# Sheet2.net
KiCad netlist of a schematic drawn in Altium Designer
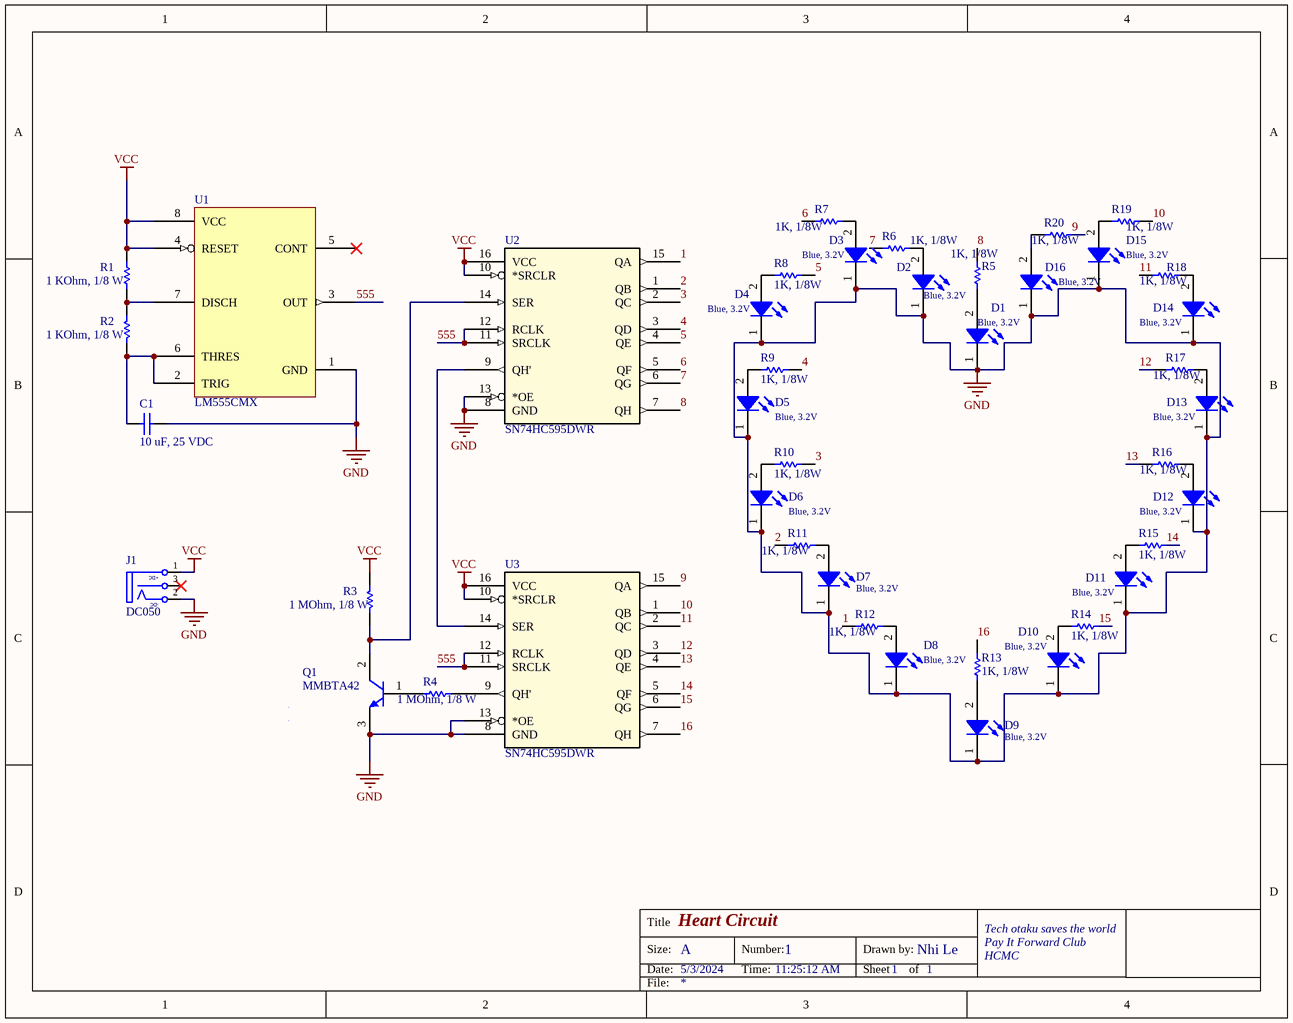
[diagram p0: Sheet2.SchDoc]

(export (version "E")
  (design (tool "Eeschema 10.0.6"))
  (components
    (comp (ref "C1")
      (value "10 uF, 25 VDC")
      (footprint "CAP_0805")
      (description "CAP, size 0805, 10 uF, 25 VDC")
      (fields (field (name "TOLERANCE") "+/-10%"))
      (libsource (lib "Altium_Ceramic_Cap") (part "0108051061025"))
    )
    (comp (ref "D1")
      (value "Blue, 3.2V")
      (footprint "WL-SMCW_0805")
      (description "WL-SMCW SMT Mono-color Chip LED Waterclear, size 0805, Blue, 3.2V, 140deg")
      (libsource (lib "Altium_LED") (part "160805BlueClear"))
    )
    (comp (ref "D2")
      (value "Blue, 3.2V")
      (footprint "WL-SMCW_0805")
      (description "WL-SMCW SMT Mono-color Chip LED Waterclear, size 0805, Blue, 3.2V, 140deg")
      (libsource (lib "Altium_LED") (part "160805BlueClear"))
    )
    (comp (ref "D3")
      (value "Blue, 3.2V")
      (footprint "WL-SMCW_0805")
      (description "WL-SMCW SMT Mono-color Chip LED Waterclear, size 0805, Blue, 3.2V, 140deg")
      (libsource (lib "Altium_LED") (part "160805BlueClear"))
    )
    (comp (ref "D4")
      (value "Blue, 3.2V")
      (footprint "WL-SMCW_0805")
      (description "WL-SMCW SMT Mono-color Chip LED Waterclear, size 0805, Blue, 3.2V, 140deg")
      (libsource (lib "Altium_LED") (part "160805BlueClear"))
    )
    (comp (ref "D5")
      (value "Blue, 3.2V")
      (footprint "WL-SMCW_0805")
      (description "WL-SMCW SMT Mono-color Chip LED Waterclear, size 0805, Blue, 3.2V, 140deg")
      (libsource (lib "Altium_LED") (part "160805BlueClear"))
    )
    (comp (ref "D6")
      (value "Blue, 3.2V")
      (footprint "WL-SMCW_0805")
      (description "WL-SMCW SMT Mono-color Chip LED Waterclear, size 0805, Blue, 3.2V, 140deg")
      (libsource (lib "Altium_LED") (part "160805BlueClear"))
    )
    (comp (ref "D7")
      (value "Blue, 3.2V")
      (footprint "WL-SMCW_0805")
      (description "WL-SMCW SMT Mono-color Chip LED Waterclear, size 0805, Blue, 3.2V, 140deg")
      (libsource (lib "Altium_LED") (part "160805BlueClear"))
    )
    (comp (ref "D8")
      (value "Blue, 3.2V")
      (footprint "WL-SMCW_0805")
      (description "WL-SMCW SMT Mono-color Chip LED Waterclear, size 0805, Blue, 3.2V, 140deg")
      (libsource (lib "Altium_LED") (part "160805BlueClear"))
    )
    (comp (ref "D9")
      (value "Blue, 3.2V")
      (footprint "WL-SMCW_0805")
      (description "WL-SMCW SMT Mono-color Chip LED Waterclear, size 0805, Blue, 3.2V, 140deg")
      (libsource (lib "Altium_LED") (part "160805BlueClear"))
    )
    (comp (ref "D10")
      (value "Blue, 3.2V")
      (footprint "WL-SMCW_0805")
      (description "WL-SMCW SMT Mono-color Chip LED Waterclear, size 0805, Blue, 3.2V, 140deg")
      (libsource (lib "Altium_LED") (part "160805BlueClear"))
    )
    (comp (ref "D11")
      (value "Blue, 3.2V")
      (footprint "WL-SMCW_0805")
      (description "WL-SMCW SMT Mono-color Chip LED Waterclear, size 0805, Blue, 3.2V, 140deg")
      (libsource (lib "Altium_LED") (part "160805BlueClear"))
    )
    (comp (ref "D12")
      (value "Blue, 3.2V")
      (footprint "WL-SMCW_0805")
      (description "WL-SMCW SMT Mono-color Chip LED Waterclear, size 0805, Blue, 3.2V, 140deg")
      (libsource (lib "Altium_LED") (part "160805BlueClear"))
    )
    (comp (ref "D13")
      (value "Blue, 3.2V")
      (footprint "WL-SMCW_0805")
      (description "WL-SMCW SMT Mono-color Chip LED Waterclear, size 0805, Blue, 3.2V, 140deg")
      (libsource (lib "Altium_LED") (part "160805BlueClear"))
    )
    (comp (ref "D14")
      (value "Blue, 3.2V")
      (footprint "WL-SMCW_0805")
      (description "WL-SMCW SMT Mono-color Chip LED Waterclear, size 0805, Blue, 3.2V, 140deg")
      (libsource (lib "Altium_LED") (part "160805BlueClear"))
    )
    (comp (ref "D15")
      (value "Blue, 3.2V")
      (footprint "WL-SMCW_0805")
      (description "WL-SMCW SMT Mono-color Chip LED Waterclear, size 0805, Blue, 3.2V, 140deg")
      (libsource (lib "Altium_LED") (part "160805BlueClear"))
    )
    (comp (ref "D16")
      (value "Blue, 3.2V")
      (footprint "WL-SMCW_0805")
      (description "WL-SMCW SMT Mono-color Chip LED Waterclear, size 0805, Blue, 3.2V, 140deg")
      (libsource (lib "Altium_LED") (part "160805BlueClear"))
    )
    (comp (ref "J1")
      (value "DC050")
      (footprint "DC050")
      (fields (field (name "MANUFACTURER") "OEM"))
      (libsource (lib "Altium_AC_DC_Jack") (part "DC050"))
    )
    (comp (ref "Q1")
      (value "MMBTA42")
      (footprint "MMBT-SOT23")
      (description "TRANS NPN, 300V, 0.5A, SOT23-3")
      (libsource (lib "Altium_BJT") (part "MMBTA42"))
    )
    (comp (ref "R1")
      (value "1 KOhm, 1/8 W")
      (footprint "RESISTOR_0805")
      (description "RES, size 0805, 1 KOhm, 1/8 W")
      (libsource (lib "Altium_Resistor") (part "0008051021"))
    )
    (comp (ref "R2")
      (value "1 KOhm, 1/8 W")
      (footprint "RESISTOR_0805")
      (description "RES, size 0805, 1 KOhm, 1/8 W")
      (libsource (lib "Altium_Resistor") (part "0008051021"))
    )
    (comp (ref "R3")
      (value "1 MOhm, 1/8 W")
      (footprint "RESISTOR_0805")
      (description "RES, size 0805, 1 MOhm, 1/8 W")
      (libsource (lib "Altium_Resistor") (part "0008051051"))
    )
    (comp (ref "R4")
      (value "1 MOhm, 1/8 W")
      (footprint "RESISTOR_0805")
      (description "RES, size 0805, 1 MOhm, 1/8 W")
      (libsource (lib "Altium_Resistor") (part "0008051051"))
    )
    (comp (ref "R5")
      (value "1K, 1/8W")
      (footprint "RESISTOR_0805")
      (description "RES, size 0805, 1 KOhm, 1/8 W")
      (libsource (lib "Altium_Resistor") (part "0008051021"))
    )
    (comp (ref "R6")
      (value "1K, 1/8W")
      (footprint "RESISTOR_0805")
      (description "RES, size 0805, 1 KOhm, 1/8 W")
      (libsource (lib "Altium_Resistor") (part "0008051021"))
    )
    (comp (ref "R7")
      (value "1K, 1/8W")
      (footprint "RESISTOR_0805")
      (description "RES, size 0805, 1 KOhm, 1/8 W")
      (libsource (lib "Altium_Resistor") (part "0008051021"))
    )
    (comp (ref "R8")
      (value "1K, 1/8W")
      (footprint "RESISTOR_0805")
      (description "RES, size 0805, 1 KOhm, 1/8 W")
      (libsource (lib "Altium_Resistor") (part "0008051021"))
    )
    (comp (ref "R9")
      (value "1K, 1/8W")
      (footprint "RESISTOR_0805")
      (description "RES, size 0805, 1 KOhm, 1/8 W")
      (libsource (lib "Altium_Resistor") (part "0008051021"))
    )
    (comp (ref "R10")
      (value "1K, 1/8W")
      (footprint "RESISTOR_0805")
      (description "RES, size 0805, 1 KOhm, 1/8 W")
      (libsource (lib "Altium_Resistor") (part "0008051021"))
    )
    (comp (ref "R11")
      (value "1K, 1/8W")
      (footprint "RESISTOR_0805")
      (description "RES, size 0805, 1 KOhm, 1/8 W")
      (libsource (lib "Altium_Resistor") (part "0008051021"))
    )
    (comp (ref "R12")
      (value "1K, 1/8W")
      (footprint "RESISTOR_0805")
      (description "RES, size 0805, 1 KOhm, 1/8 W")
      (libsource (lib "Altium_Resistor") (part "0008051021"))
    )
    (comp (ref "R13")
      (value "1K, 1/8W")
      (footprint "RESISTOR_0805")
      (description "RES, size 0805, 1 KOhm, 1/8 W")
      (libsource (lib "Altium_Resistor") (part "0008051021"))
    )
    (comp (ref "R14")
      (value "1K, 1/8W")
      (footprint "RESISTOR_0805")
      (description "RES, size 0805, 1 KOhm, 1/8 W")
      (libsource (lib "Altium_Resistor") (part "0008051021"))
    )
    (comp (ref "R15")
      (value "1K, 1/8W")
      (footprint "RESISTOR_0805")
      (description "RES, size 0805, 1 KOhm, 1/8 W")
      (libsource (lib "Altium_Resistor") (part "0008051021"))
    )
    (comp (ref "R16")
      (value "1K, 1/8W")
      (footprint "RESISTOR_0805")
      (description "RES, size 0805, 1 KOhm, 1/8 W")
      (libsource (lib "Altium_Resistor") (part "0008051021"))
    )
    (comp (ref "R17")
      (value "1K, 1/8W")
      (footprint "RESISTOR_0805")
      (description "RES, size 0805, 1 KOhm, 1/8 W")
      (libsource (lib "Altium_Resistor") (part "0008051021"))
    )
    (comp (ref "R18")
      (value "1K, 1/8W")
      (footprint "RESISTOR_0805")
      (description "RES, size 0805, 1 KOhm, 1/8 W")
      (libsource (lib "Altium_Resistor") (part "0008051021"))
    )
    (comp (ref "R19")
      (value "1K, 1/8W")
      (footprint "RESISTOR_0805")
      (description "RES, size 0805, 1 KOhm, 1/8 W")
      (libsource (lib "Altium_Resistor") (part "0008051021"))
    )
    (comp (ref "R20")
      (value "1K, 1/8W")
      (footprint "RESISTOR_0805")
      (description "RES, size 0805, 1 KOhm, 1/8 W")
      (libsource (lib "Altium_Resistor") (part "0008051021"))
    )
    (comp (ref "U1")
      (value "LM555CMX")
      (footprint "LM555CMX")
      (description "Timers & Support Products TIMER")
      (fields
        (field (name "MANUFACTURER") "Texas Instruments")
        (field (name "MANUFACTURER PART NUMBER") "LM555CMX/NOPB")
      )
      (libsource (lib "Other") (part "LM555CMX"))
    )
    (comp (ref "U2")
      (value "SN74HC595DWR")
      (footprint "DW16")
      (description "No Description Available")
      (libsource (lib "SN74HC595DWR") (part "SN74HC595DWR"))
    )
    (comp (ref "U3")
      (value "SN74HC595DWR")
      (footprint "DW16")
      (description "No Description Available")
      (libsource (lib "SN74HC595DWR") (part "SN74HC595DWR"))
    )
  )
  (nets
    (net (code "1") (name "/1") (class "Default")
      (node (ref "R12") (pin "2") (pinfunction "2_2") (pintype "passive"))
      (node (ref "U2") (pin "15") (pinfunction "QA_15") (pintype "output"))
    )
    (net (code "2") (name "/2") (class "Default")
      (node (ref "R11") (pin "2") (pinfunction "2_2") (pintype "passive"))
      (node (ref "U2") (pin "1") (pinfunction "QB_1") (pintype "output"))
    )
    (net (code "3") (name "/3") (class "Default")
      (node (ref "R10") (pin "2") (pinfunction "2_2") (pintype "passive"))
      (node (ref "U2") (pin "2") (pinfunction "QC_2") (pintype "output"))
    )
    (net (code "4") (name "/4") (class "Default")
      (node (ref "R9") (pin "2") (pinfunction "2_2") (pintype "passive"))
      (node (ref "U2") (pin "3") (pinfunction "QD_3") (pintype "output"))
    )
    (net (code "5") (name "/5") (class "Default")
      (node (ref "R8") (pin "2") (pinfunction "2_2") (pintype "passive"))
      (node (ref "U2") (pin "4") (pinfunction "QE_4") (pintype "output"))
    )
    (net (code "6") (name "/6") (class "Default")
      (node (ref "R7") (pin "2") (pinfunction "2_2") (pintype "passive"))
      (node (ref "U2") (pin "5") (pinfunction "QF_5") (pintype "output"))
    )
    (net (code "7") (name "/7") (class "Default")
      (node (ref "R6") (pin "2") (pinfunction "2_2") (pintype "passive"))
      (node (ref "U2") (pin "6") (pinfunction "QG_6") (pintype "output"))
    )
    (net (code "8") (name "/8") (class "Default")
      (node (ref "R5") (pin "1") (pinfunction "1_1") (pintype "passive"))
      (node (ref "U2") (pin "7") (pinfunction "QH_7") (pintype "output"))
    )
    (net (code "9") (name "/9") (class "Default")
      (node (ref "R20") (pin "2") (pinfunction "2_2") (pintype "passive"))
      (node (ref "U3") (pin "15") (pinfunction "QA_15") (pintype "output"))
    )
    (net (code "10") (name "/10") (class "Default")
      (node (ref "R19") (pin "2") (pinfunction "2_2") (pintype "passive"))
      (node (ref "U3") (pin "1") (pinfunction "QB_1") (pintype "output"))
    )
    (net (code "11") (name "/11") (class "Default")
      (node (ref "R18") (pin "2") (pinfunction "2_2") (pintype "passive"))
      (node (ref "U3") (pin "2") (pinfunction "QC_2") (pintype "output"))
    )
    (net (code "12") (name "/12") (class "Default")
      (node (ref "R17") (pin "2") (pinfunction "2_2") (pintype "passive"))
      (node (ref "U3") (pin "3") (pinfunction "QD_3") (pintype "output"))
    )
    (net (code "13") (name "/13") (class "Default")
      (node (ref "R16") (pin "2") (pinfunction "2_2") (pintype "passive"))
      (node (ref "U3") (pin "4") (pinfunction "QE_4") (pintype "output"))
    )
    (net (code "14") (name "/14") (class "Default")
      (node (ref "R15") (pin "2") (pinfunction "2_2") (pintype "passive"))
      (node (ref "U3") (pin "5") (pinfunction "QF_5") (pintype "output"))
    )
    (net (code "15") (name "/15") (class "Default")
      (node (ref "R14") (pin "2") (pinfunction "2_2") (pintype "passive"))
      (node (ref "U3") (pin "6") (pinfunction "QG_6") (pintype "output"))
    )
    (net (code "16") (name "/16") (class "Default")
      (node (ref "R13") (pin "2") (pinfunction "2_2") (pintype "passive"))
      (node (ref "U3") (pin "7") (pinfunction "QH_7") (pintype "output"))
    )
    (net (code "17") (name "/555") (class "Default")
      (node (ref "U1") (pin "3") (pinfunction "OUT_3") (pintype "output"))
      (node (ref "U2") (pin "11") (pinfunction "SRCLK_11") (pintype "input"))
      (node (ref "U2") (pin "12") (pinfunction "RCLK_12") (pintype "input"))
      (node (ref "U3") (pin "11") (pinfunction "SRCLK_11") (pintype "input"))
      (node (ref "U3") (pin "12") (pinfunction "RCLK_12") (pintype "input"))
    )
    (net (code "18") (name "GND") (class "Default")
      (node (ref "C1") (pin "2") (pinfunction "2_2") (pintype "passive"))
      (node (ref "D1") (pin "1") (pinfunction "K_1") (pintype "passive"))
      (node (ref "D10") (pin "1") (pinfunction "K_1") (pintype "passive"))
      (node (ref "D11") (pin "1") (pinfunction "K_1") (pintype "passive"))
      (node (ref "D12") (pin "1") (pinfunction "K_1") (pintype "passive"))
      (node (ref "D13") (pin "1") (pinfunction "K_1") (pintype "passive"))
      (node (ref "D14") (pin "1") (pinfunction "K_1") (pintype "passive"))
      (node (ref "D15") (pin "1") (pinfunction "K_1") (pintype "passive"))
      (node (ref "D16") (pin "1") (pinfunction "K_1") (pintype "passive"))
      (node (ref "D2") (pin "1") (pinfunction "K_1") (pintype "passive"))
      (node (ref "D3") (pin "1") (pinfunction "K_1") (pintype "passive"))
      (node (ref "D4") (pin "1") (pinfunction "K_1") (pintype "passive"))
      (node (ref "D5") (pin "1") (pinfunction "K_1") (pintype "passive"))
      (node (ref "D6") (pin "1") (pinfunction "K_1") (pintype "passive"))
      (node (ref "D7") (pin "1") (pinfunction "K_1") (pintype "passive"))
      (node (ref "D8") (pin "1") (pinfunction "K_1") (pintype "passive"))
      (node (ref "D9") (pin "1") (pinfunction "K_1") (pintype "passive"))
      (node (ref "J1") (pin "2") (pinfunction "TN_2") (pintype "passive"))
      (node (ref "Q1") (pin "3") (pinfunction "E_3") (pintype "passive"))
      (node (ref "U1") (pin "1") (pinfunction "GND_1") (pintype "power_in"))
      (node (ref "U2") (pin "13") (pinfunction "*OE_13") (pintype "input"))
      (node (ref "U2") (pin "8") (pinfunction "GND_8") (pintype "power_in"))
      (node (ref "U3") (pin "13") (pinfunction "*OE_13") (pintype "input"))
      (node (ref "U3") (pin "8") (pinfunction "GND_8") (pintype "power_in"))
    )
    (net (code "19") (name "Net-(D1-A)") (class "Default")
      (node (ref "D1") (pin "2") (pinfunction "A_2") (pintype "passive"))
      (node (ref "R5") (pin "2") (pinfunction "2_2") (pintype "passive"))
    )
    (net (code "20") (name "Net-(D2-A)") (class "Default")
      (node (ref "D2") (pin "2") (pinfunction "A_2") (pintype "passive"))
      (node (ref "R6") (pin "1") (pinfunction "1_1") (pintype "passive"))
    )
    (net (code "21") (name "Net-(D3-A)") (class "Default")
      (node (ref "D3") (pin "2") (pinfunction "A_2") (pintype "passive"))
      (node (ref "R7") (pin "1") (pinfunction "1_1") (pintype "passive"))
    )
    (net (code "22") (name "Net-(D4-A)") (class "Default")
      (node (ref "D4") (pin "2") (pinfunction "A_2") (pintype "passive"))
      (node (ref "R8") (pin "1") (pinfunction "1_1") (pintype "passive"))
    )
    (net (code "23") (name "Net-(D5-A)") (class "Default")
      (node (ref "D5") (pin "2") (pinfunction "A_2") (pintype "passive"))
      (node (ref "R9") (pin "1") (pinfunction "1_1") (pintype "passive"))
    )
    (net (code "24") (name "Net-(D6-A)") (class "Default")
      (node (ref "D6") (pin "2") (pinfunction "A_2") (pintype "passive"))
      (node (ref "R10") (pin "1") (pinfunction "1_1") (pintype "passive"))
    )
    (net (code "25") (name "Net-(D7-A)") (class "Default")
      (node (ref "D7") (pin "2") (pinfunction "A_2") (pintype "passive"))
      (node (ref "R11") (pin "1") (pinfunction "1_1") (pintype "passive"))
    )
    (net (code "26") (name "Net-(D8-A)") (class "Default")
      (node (ref "D8") (pin "2") (pinfunction "A_2") (pintype "passive"))
      (node (ref "R12") (pin "1") (pinfunction "1_1") (pintype "passive"))
    )
    (net (code "27") (name "Net-(D9-A)") (class "Default")
      (node (ref "D9") (pin "2") (pinfunction "A_2") (pintype "passive"))
      (node (ref "R13") (pin "1") (pinfunction "1_1") (pintype "passive"))
    )
    (net (code "28") (name "Net-(D10-A)") (class "Default")
      (node (ref "D10") (pin "2") (pinfunction "A_2") (pintype "passive"))
      (node (ref "R14") (pin "1") (pinfunction "1_1") (pintype "passive"))
    )
    (net (code "29") (name "Net-(D11-A)") (class "Default")
      (node (ref "D11") (pin "2") (pinfunction "A_2") (pintype "passive"))
      (node (ref "R15") (pin "1") (pinfunction "1_1") (pintype "passive"))
    )
    (net (code "30") (name "Net-(D12-A)") (class "Default")
      (node (ref "D12") (pin "2") (pinfunction "A_2") (pintype "passive"))
      (node (ref "R16") (pin "1") (pinfunction "1_1") (pintype "passive"))
    )
    (net (code "31") (name "Net-(D13-A)") (class "Default")
      (node (ref "D13") (pin "2") (pinfunction "A_2") (pintype "passive"))
      (node (ref "R17") (pin "1") (pinfunction "1_1") (pintype "passive"))
    )
    (net (code "32") (name "Net-(D14-A)") (class "Default")
      (node (ref "D14") (pin "2") (pinfunction "A_2") (pintype "passive"))
      (node (ref "R18") (pin "1") (pinfunction "1_1") (pintype "passive"))
    )
    (net (code "33") (name "Net-(D15-A)") (class "Default")
      (node (ref "D15") (pin "2") (pinfunction "A_2") (pintype "passive"))
      (node (ref "R19") (pin "1") (pinfunction "1_1") (pintype "passive"))
    )
    (net (code "34") (name "Net-(D16-A)") (class "Default")
      (node (ref "D16") (pin "2") (pinfunction "A_2") (pintype "passive"))
      (node (ref "R20") (pin "1") (pinfunction "1_1") (pintype "passive"))
    )
    (net (code "35") (name "Net-(Q1-B)") (class "Default")
      (node (ref "Q1") (pin "1") (pinfunction "B_1") (pintype "passive"))
      (node (ref "R4") (pin "1") (pinfunction "1_1") (pintype "passive"))
    )
    (net (code "36") (name "Net-(Q1-C)") (class "Default")
      (node (ref "Q1") (pin "2") (pinfunction "C_2") (pintype "passive"))
      (node (ref "R3") (pin "1") (pinfunction "1_1") (pintype "passive"))
      (node (ref "U2") (pin "14") (pinfunction "SER_14") (pintype "input"))
    )
    (net (code "37") (name "Net-(U1-DISCH)") (class "Default")
      (node (ref "R1") (pin "1") (pinfunction "1_1") (pintype "passive"))
      (node (ref "R2") (pin "2") (pinfunction "2_2") (pintype "passive"))
      (node (ref "U1") (pin "7") (pinfunction "DISCH_7") (pintype "passive"))
    )
    (net (code "38") (name "Net-(U1-THRES)") (class "Default")
      (node (ref "C1") (pin "1") (pinfunction "1_1") (pintype "passive"))
      (node (ref "R2") (pin "1") (pinfunction "1_1") (pintype "passive"))
      (node (ref "U1") (pin "2") (pinfunction "TRIG_2") (pintype "passive"))
      (node (ref "U1") (pin "6") (pinfunction "THRES_6") (pintype "passive"))
    )
    (net (code "39") (name "Net-(U2-QH')") (class "Default")
      (node (ref "U2") (pin "9") (pinfunction "QH'_9") (pintype "output"))
      (node (ref "U3") (pin "14") (pinfunction "SER_14") (pintype "input"))
    )
    (net (code "40") (name "Net-(U3-QH')") (class "Default")
      (node (ref "R4") (pin "2") (pinfunction "2_2") (pintype "passive"))
      (node (ref "U3") (pin "9") (pinfunction "QH'_9") (pintype "output"))
    )
    (net (code "41") (name "VCC") (class "Default")
      (node (ref "J1") (pin "1") (pinfunction "T_1") (pintype "passive"))
      (node (ref "R1") (pin "2") (pinfunction "2_2") (pintype "passive"))
      (node (ref "R3") (pin "2") (pinfunction "2_2") (pintype "passive"))
      (node (ref "U1") (pin "4") (pinfunction "RESET_4") (pintype "input"))
      (node (ref "U1") (pin "8") (pinfunction "VCC_8") (pintype "power_in"))
      (node (ref "U2") (pin "10") (pinfunction "*SRCLR_10") (pintype "input"))
      (node (ref "U2") (pin "16") (pinfunction "VCC_16") (pintype "power_in"))
      (node (ref "U3") (pin "10") (pinfunction "*SRCLR_10") (pintype "input"))
      (node (ref "U3") (pin "16") (pinfunction "VCC_16") (pintype "power_in"))
    )
    (net (code "42") (name "unconnected-(J1-S-Pad3)") (class "Default")
      (node (ref "J1") (pin "3") (pinfunction "S_3") (pintype "power_in+no_connect"))
    )
    (net (code "43") (name "unconnected-(U1-CONT-Pad5)") (class "Default")
      (node (ref "U1") (pin "5") (pinfunction "CONT_5") (pintype "passive+no_connect"))
    )
  )
)
